# invert_amp_filters.net
KiCad netlist of a schematic drawn in EAGLE
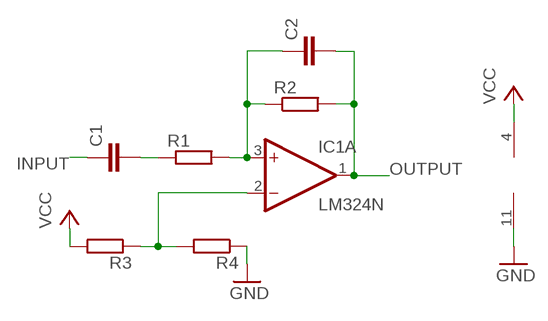
[diagram p0: schematic, sheet 1]

(export (version "E")
  (design (tool "Eeschema 10.0.6"))
  (components
    (comp (ref "C1")
      (value "C-EU025-025X050")
      (footprint "eagle-import:C025-025X050")
      (libsource (lib "eagle-import") (part "C-EU025-025X050"))
    )
    (comp (ref "C2")
      (value "C-EU025-025X050")
      (footprint "eagle-import:C025-025X050")
      (libsource (lib "eagle-import") (part "C-EU025-025X050"))
    )
    (comp (ref "IC1")
      (value "LM324N")
      (footprint "eagle-import:DIL14")
      (libsource (lib "eagle-import") (part "LM324N"))
    )
    (comp (ref "R1")
      (value "R-EU_0204/7")
      (footprint "eagle-import:0204_7")
      (libsource (lib "eagle-import") (part "R-EU_0204/7"))
    )
    (comp (ref "R2")
      (value "R-EU_0204/7")
      (footprint "eagle-import:0204_7")
      (libsource (lib "eagle-import") (part "R-EU_0204/7"))
    )
    (comp (ref "R3")
      (value "R-EU_0204/7")
      (footprint "eagle-import:0204_7")
      (libsource (lib "eagle-import") (part "R-EU_0204/7"))
    )
    (comp (ref "R4")
      (value "R-EU_0204/7")
      (footprint "eagle-import:0204_7")
      (libsource (lib "eagle-import") (part "R-EU_0204/7"))
    )
  )
  (nets
    (net (code "1") (name "/INPUT") (class "Default")
      (node (ref "C1") (pin "1") (pinfunction "1_1") (pintype "passive"))
    )
    (net (code "2") (name "/OUTPUT") (class "Default")
      (node (ref "C2") (pin "2") (pinfunction "2_2") (pintype "passive"))
      (node (ref "IC1") (pin "1") (pinfunction "OUT_1") (pintype "output"))
      (node (ref "R2") (pin "2") (pinfunction "2_2") (pintype "passive"))
    )
    (net (code "3") (name "GND") (class "Default")
      (node (ref "IC1") (pin "11") (pinfunction "V-_11") (pintype "power_in"))
      (node (ref "R4") (pin "1") (pinfunction "1_1") (pintype "passive"))
    )
    (net (code "4") (name "Net-(C1-Pad2)") (class "Default")
      (node (ref "C1") (pin "2") (pinfunction "2_2") (pintype "passive"))
      (node (ref "R1") (pin "1") (pinfunction "1_1") (pintype "passive"))
    )
    (net (code "5") (name "Net-(IC1A-+IN)") (class "Default")
      (node (ref "C2") (pin "1") (pinfunction "1_1") (pintype "passive"))
      (node (ref "IC1") (pin "3") (pinfunction "+IN_3") (pintype "input"))
      (node (ref "R1") (pin "2") (pinfunction "2_2") (pintype "passive"))
      (node (ref "R2") (pin "1") (pinfunction "1_1") (pintype "passive"))
    )
    (net (code "6") (name "Net-(IC1A--IN)") (class "Default")
      (node (ref "IC1") (pin "2") (pinfunction "-IN_2") (pintype "input"))
      (node (ref "R3") (pin "1") (pinfunction "1_1") (pintype "passive"))
      (node (ref "R4") (pin "2") (pinfunction "2_2") (pintype "passive"))
    )
    (net (code "7") (name "VCC") (class "Default")
      (node (ref "IC1") (pin "4") (pinfunction "V+_4") (pintype "power_in"))
      (node (ref "R3") (pin "2") (pinfunction "2_2") (pintype "passive"))
    )
  )
)
